# SCH_Eagle-Blinkyy_2025-12-10.net
KiCad netlist of a schematic drawn in EasyEDA
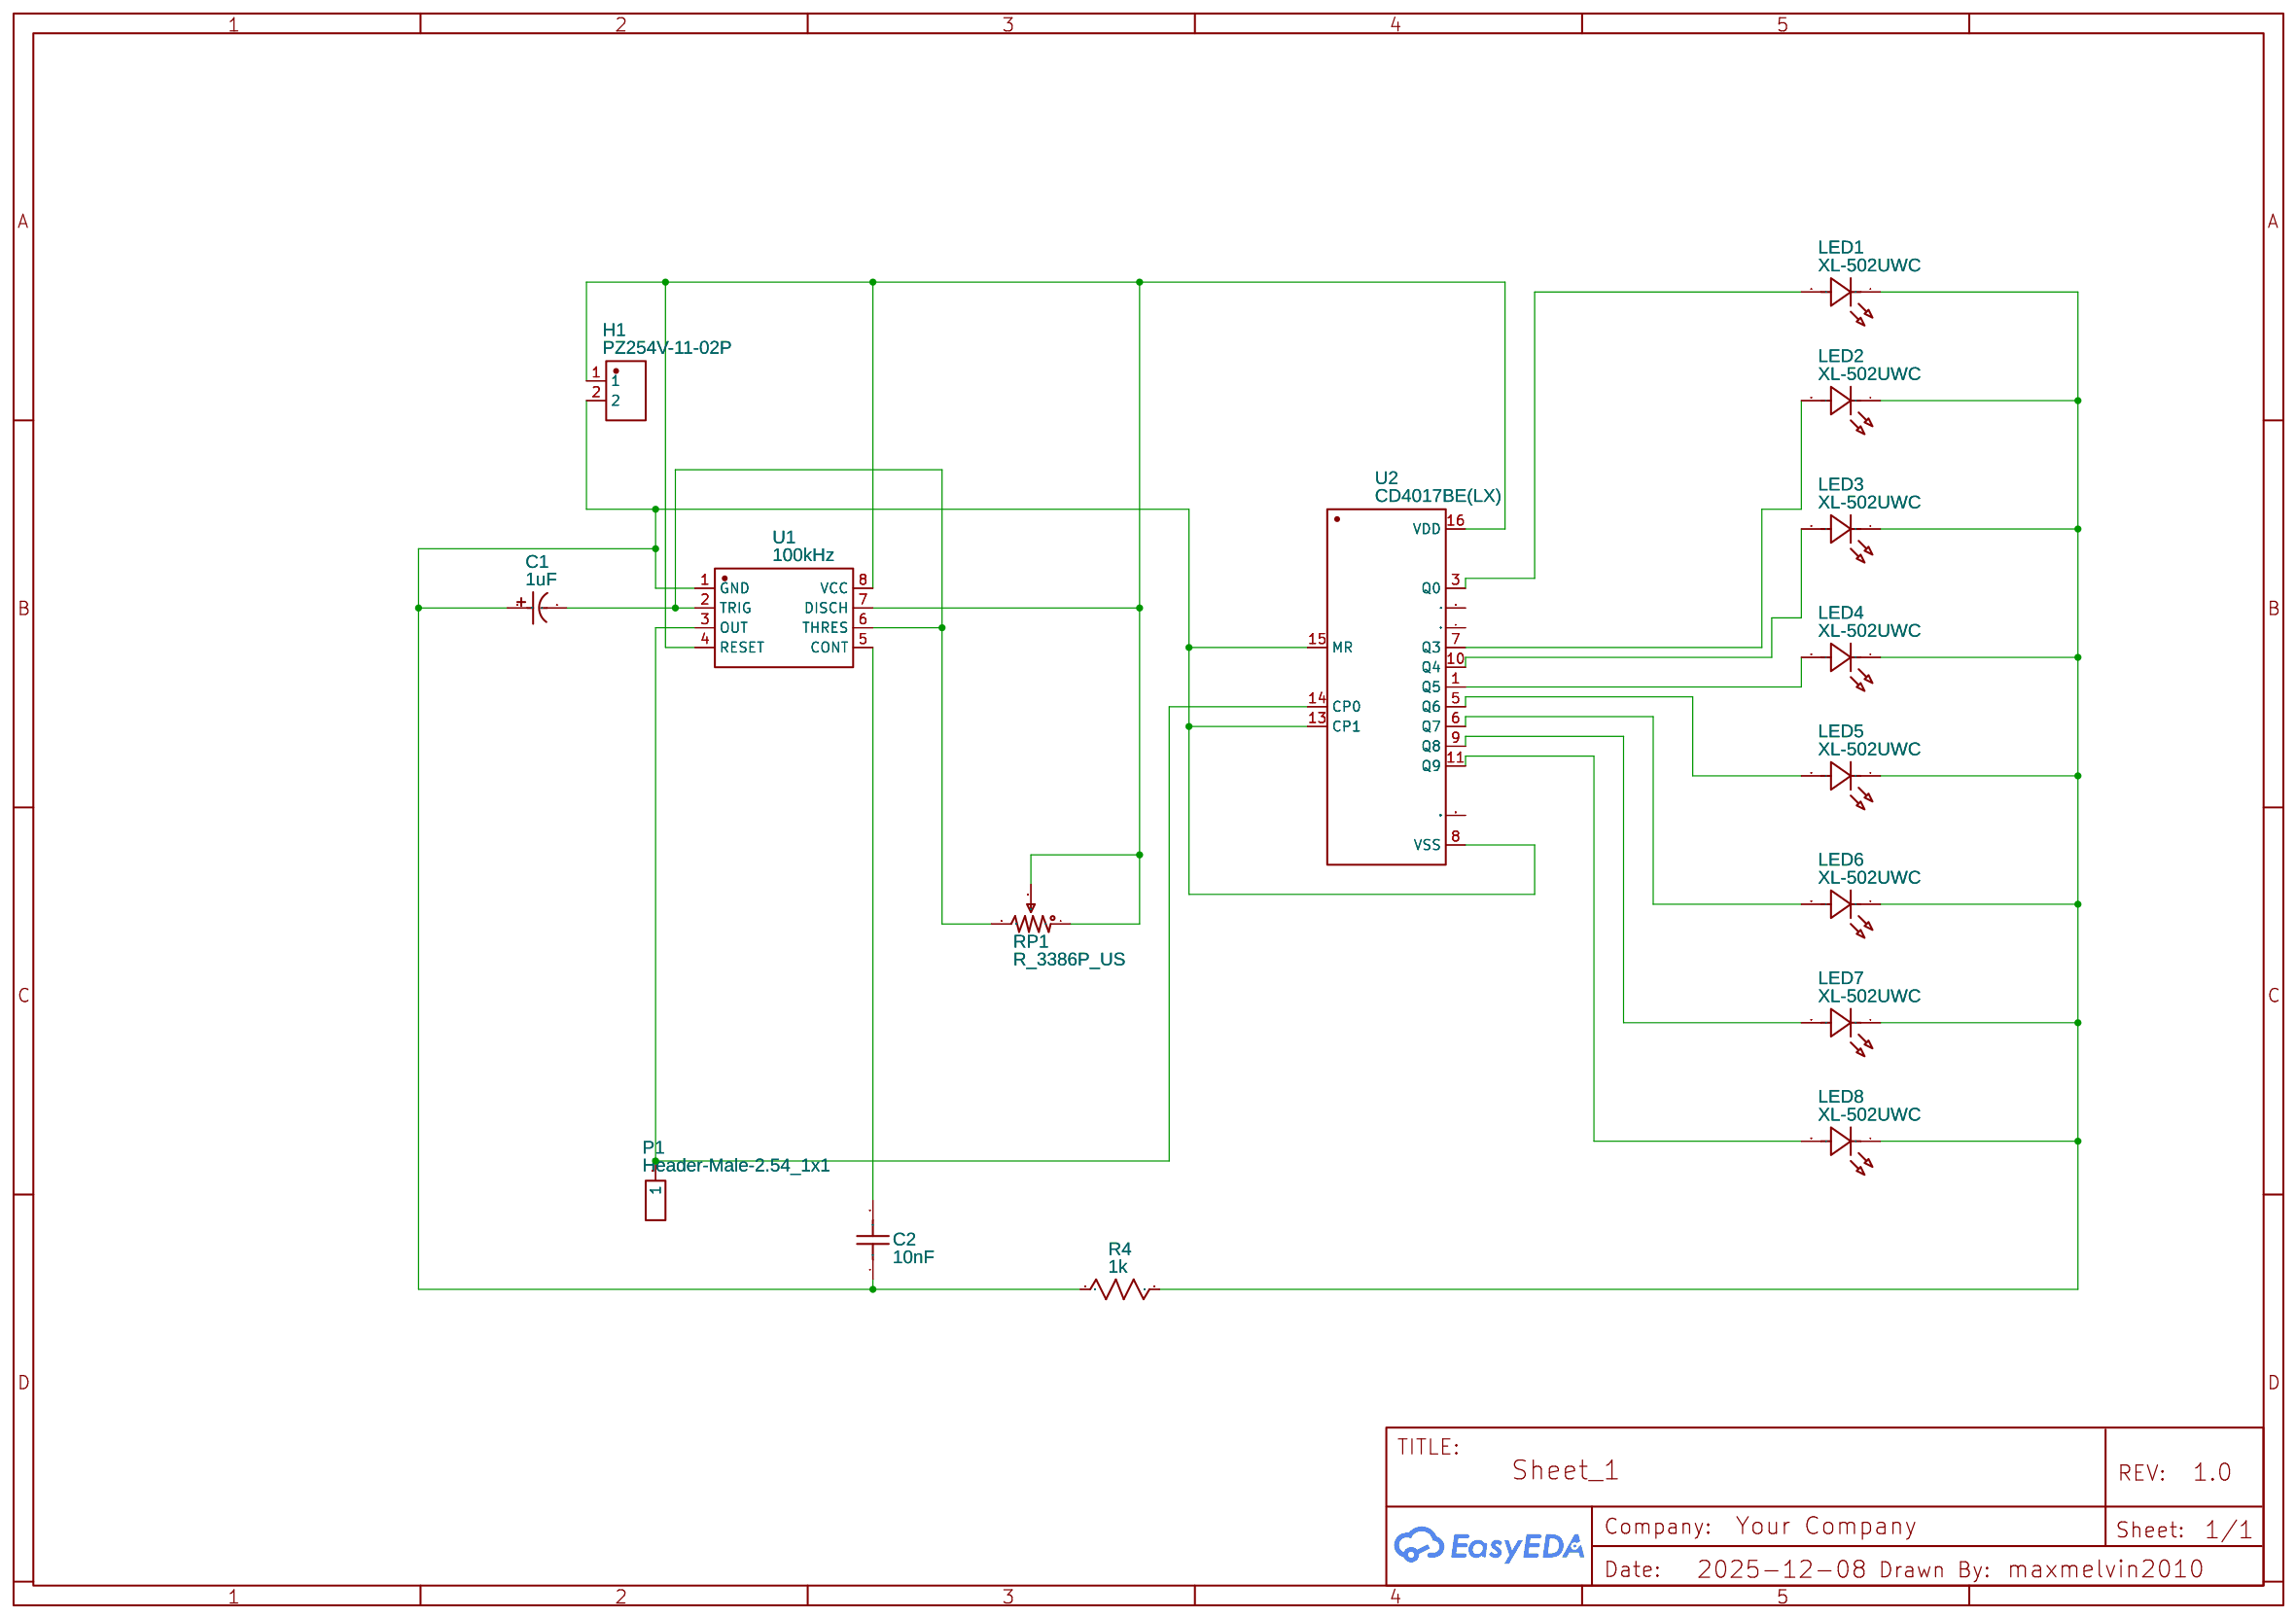
[diagram p0: schematic sheet]

(export (version "E")
  (design (tool "Eeschema 10.0.6"))
  (components
    (comp (ref "C1")
      (value "1uF")
      (fields (field (name "Manufacturer Part") "KF010M050C110A") (field (name "Manufacturer") "CapXon(丰宾)"))
      (libsource (lib "") (part "KF010M050C110A"))
    )
    (comp (ref "C2")
      (value "10nF")
      (fields (field (name "Manufacturer Part") "N09F1B103MN0B0S0N0") (field (name "Manufacturer") "STE(松田)"))
      (libsource (lib "") (part "N09F1B103MN0B0S0N0"))
    )
    (comp (ref "H1")
      (value "PZ254V-11-02P")
      (fields (field (name "Manufacturer") "XFCN(兴飞)"))
      (libsource (lib "") (part "PZ254V-11-02P"))
    )
    (comp (ref "LED1")
      (value "XL-502UWC")
      (fields (field (name "Manufacturer") "XINGLIGHT(成兴光)"))
      (libsource (lib "") (part "XL-502UWC"))
    )
    (comp (ref "LED2")
      (value "XL-502UWC")
      (fields (field (name "Manufacturer") "XINGLIGHT(成兴光)"))
      (libsource (lib "") (part "XL-502UWC"))
    )
    (comp (ref "LED3")
      (value "XL-502UWC")
      (fields (field (name "Manufacturer") "XINGLIGHT(成兴光)"))
      (libsource (lib "") (part "XL-502UWC"))
    )
    (comp (ref "LED4")
      (value "XL-502UWC")
      (fields (field (name "Manufacturer") "XINGLIGHT(成兴光)"))
      (libsource (lib "") (part "XL-502UWC"))
    )
    (comp (ref "LED5")
      (value "XL-502UWC")
      (fields (field (name "Manufacturer") "XINGLIGHT(成兴光)"))
      (libsource (lib "") (part "XL-502UWC"))
    )
    (comp (ref "LED6")
      (value "XL-502UWC")
      (fields (field (name "Manufacturer") "XINGLIGHT(成兴光)"))
      (libsource (lib "") (part "XL-502UWC"))
    )
    (comp (ref "LED7")
      (value "XL-502UWC")
      (fields (field (name "Manufacturer") "XINGLIGHT(成兴光)"))
      (libsource (lib "") (part "XL-502UWC"))
    )
    (comp (ref "LED8")
      (value "XL-502UWC")
      (fields (field (name "Manufacturer") "XINGLIGHT(成兴光)"))
      (libsource (lib "") (part "XL-502UWC"))
    )
    (comp (ref "P1")
      (value "Header-Male-2.54_1x1")
      (fields (field (name "Manufacturer Part") "2.54-1*1P针") (field (name "Manufacturer") "BOOMELE(博穆精密)"))
      (libsource (lib "") (part "Header-Male-2.54_1x1"))
    )
    (comp (ref "R4") (value "1k") (libsource (lib "") (part "R_1206_US")))
    (comp (ref "RP1") (value "R_3386P_US") (libsource (lib "") (part "R_3386P_US")))
    (comp (ref "U1")
      (value "100kHz")
      (fields (field (name "Manufacturer Part") "NE555P") (field (name "Manufacturer") "TI(德州仪器)"))
      (libsource (lib "") (part "NE555P"))
    )
    (comp (ref "U2")
      (value "CD4017BE(LX)")
      (fields (field (name "Manufacturer") "LX(灵星芯微)"))
      (libsource (lib "") (part "CD4017BE(LX)"))
    )
  )
  (nets
    (net (code "1") (name "Net-(LED1-A)") (class "Default")
      (node (ref "LED1") (pin "2") (pinfunction "A_2") (pintype "unspecified"))
      (node (ref "U2") (pin "3") (pinfunction "Q0_3") (pintype "unspecified"))
    )
    (net (code "2") (name "Net-(LED1-K)") (class "Default")
      (node (ref "LED1") (pin "1") (pinfunction "K_1") (pintype "unspecified"))
      (node (ref "LED2") (pin "1") (pinfunction "K_1") (pintype "unspecified"))
      (node (ref "LED3") (pin "1") (pinfunction "K_1") (pintype "unspecified"))
      (node (ref "LED4") (pin "1") (pinfunction "K_1") (pintype "unspecified"))
      (node (ref "LED5") (pin "1") (pinfunction "K_1") (pintype "unspecified"))
      (node (ref "LED6") (pin "1") (pinfunction "K_1") (pintype "unspecified"))
      (node (ref "LED7") (pin "1") (pinfunction "K_1") (pintype "unspecified"))
      (node (ref "LED8") (pin "1") (pinfunction "K_1") (pintype "unspecified"))
      (node (ref "R4") (pin "2") (pinfunction "2_2") (pintype "unspecified"))
    )
    (net (code "3") (name "Net-(LED2-A)") (class "Default")
      (node (ref "LED2") (pin "2") (pinfunction "A_2") (pintype "unspecified"))
      (node (ref "U2") (pin "7") (pinfunction "Q3_7") (pintype "unspecified"))
    )
    (net (code "4") (name "Net-(LED3-A)") (class "Default")
      (node (ref "LED3") (pin "2") (pinfunction "A_2") (pintype "unspecified"))
      (node (ref "U2") (pin "10") (pinfunction "Q4_10") (pintype "unspecified"))
    )
    (net (code "5") (name "Net-(LED4-A)") (class "Default")
      (node (ref "LED4") (pin "2") (pinfunction "A_2") (pintype "unspecified"))
      (node (ref "U2") (pin "1") (pinfunction "Q5_1") (pintype "unspecified"))
    )
    (net (code "6") (name "Net-(LED5-A)") (class "Default")
      (node (ref "LED5") (pin "2") (pinfunction "A_2") (pintype "unspecified"))
      (node (ref "U2") (pin "5") (pinfunction "Q6_5") (pintype "unspecified"))
    )
    (net (code "7") (name "Net-(LED6-A)") (class "Default")
      (node (ref "LED6") (pin "2") (pinfunction "A_2") (pintype "unspecified"))
      (node (ref "U2") (pin "6") (pinfunction "Q7_6") (pintype "unspecified"))
    )
    (net (code "8") (name "Net-(LED7-A)") (class "Default")
      (node (ref "LED7") (pin "2") (pinfunction "A_2") (pintype "unspecified"))
      (node (ref "U2") (pin "9") (pinfunction "Q8_9") (pintype "unspecified"))
    )
    (net (code "9") (name "Net-(LED8-A)") (class "Default")
      (node (ref "LED8") (pin "2") (pinfunction "A_2") (pintype "unspecified"))
      (node (ref "U2") (pin "11") (pinfunction "Q9_11") (pintype "unspecified"))
    )
    (net (code "10") (name "Net-(U1-CONT)") (class "Default")
      (node (ref "C2") (pin "2") (pinfunction "2_2") (pintype "unspecified"))
      (node (ref "U1") (pin "5") (pinfunction "CONT_5") (pintype "unspecified"))
    )
    (net (code "11") (name "Net-(U1-DISCH)") (class "Default")
      (node (ref "H1") (pin "1") (pinfunction "1_1") (pintype "unspecified"))
      (node (ref "RP1") (pin "1") (pinfunction "1_1") (pintype "unspecified"))
      (node (ref "RP1") (pin "2") (pinfunction "2_2") (pintype "unspecified"))
      (node (ref "U1") (pin "4") (pinfunction "RESET_4") (pintype "unspecified"))
      (node (ref "U1") (pin "7") (pinfunction "DISCH_7") (pintype "unspecified"))
      (node (ref "U1") (pin "8") (pinfunction "VCC_8") (pintype "unspecified"))
      (node (ref "U2") (pin "16") (pinfunction "VDD_16") (pintype "unspecified"))
    )
    (net (code "12") (name "Net-(U1-GND)") (class "Default")
      (node (ref "C1") (pin "1") (pinfunction "1_1") (pintype "input"))
      (node (ref "C2") (pin "1") (pinfunction "1_1") (pintype "unspecified"))
      (node (ref "H1") (pin "2") (pinfunction "2_2") (pintype "unspecified"))
      (node (ref "R4") (pin "1") (pinfunction "1_1") (pintype "unspecified"))
      (node (ref "U1") (pin "1") (pinfunction "GND_1") (pintype "unspecified"))
      (node (ref "U2") (pin "13") (pinfunction "CP1_13") (pintype "unspecified"))
      (node (ref "U2") (pin "15") (pinfunction "MR_15") (pintype "unspecified"))
      (node (ref "U2") (pin "8") (pinfunction "VSS_8") (pintype "unspecified"))
    )
    (net (code "13") (name "Net-(U1-OUT)") (class "Default")
      (node (ref "P1") (pin "1") (pinfunction "1_1") (pintype "input"))
      (node (ref "U1") (pin "3") (pinfunction "OUT_3") (pintype "unspecified"))
      (node (ref "U2") (pin "14") (pinfunction "CP0_14") (pintype "unspecified"))
    )
    (net (code "14") (name "Net-(U1-THRES)") (class "Default")
      (node (ref "C1") (pin "2") (pinfunction "2_2") (pintype "input"))
      (node (ref "RP1") (pin "3") (pinfunction "3_3") (pintype "unspecified"))
      (node (ref "U1") (pin "2") (pinfunction "TRIG_2") (pintype "unspecified"))
      (node (ref "U1") (pin "6") (pinfunction "THRES_6") (pintype "unspecified"))
    )
    (net (code "15") (name "unconnected-(U2-Q1-Pad2)") (class "Default")
      (node (ref "U2") (pin "2") (pinfunction "Q1_2") (pintype "unspecified"))
    )
    (net (code "16") (name "unconnected-(U2-Q2-Pad4)") (class "Default")
      (node (ref "U2") (pin "4") (pinfunction "Q2_4") (pintype "unspecified"))
    )
    (net (code "17") (name "unconnected-(U2-Q5-9-Pad12)") (class "Default")
      (node (ref "U2") (pin "12") (pinfunction "Q5-9_12") (pintype "unspecified"))
    )
  )
)
